# SCH_Sensor_circuit_design1_2023-04-27.net
KiCad netlist of a schematic drawn in EasyEDA
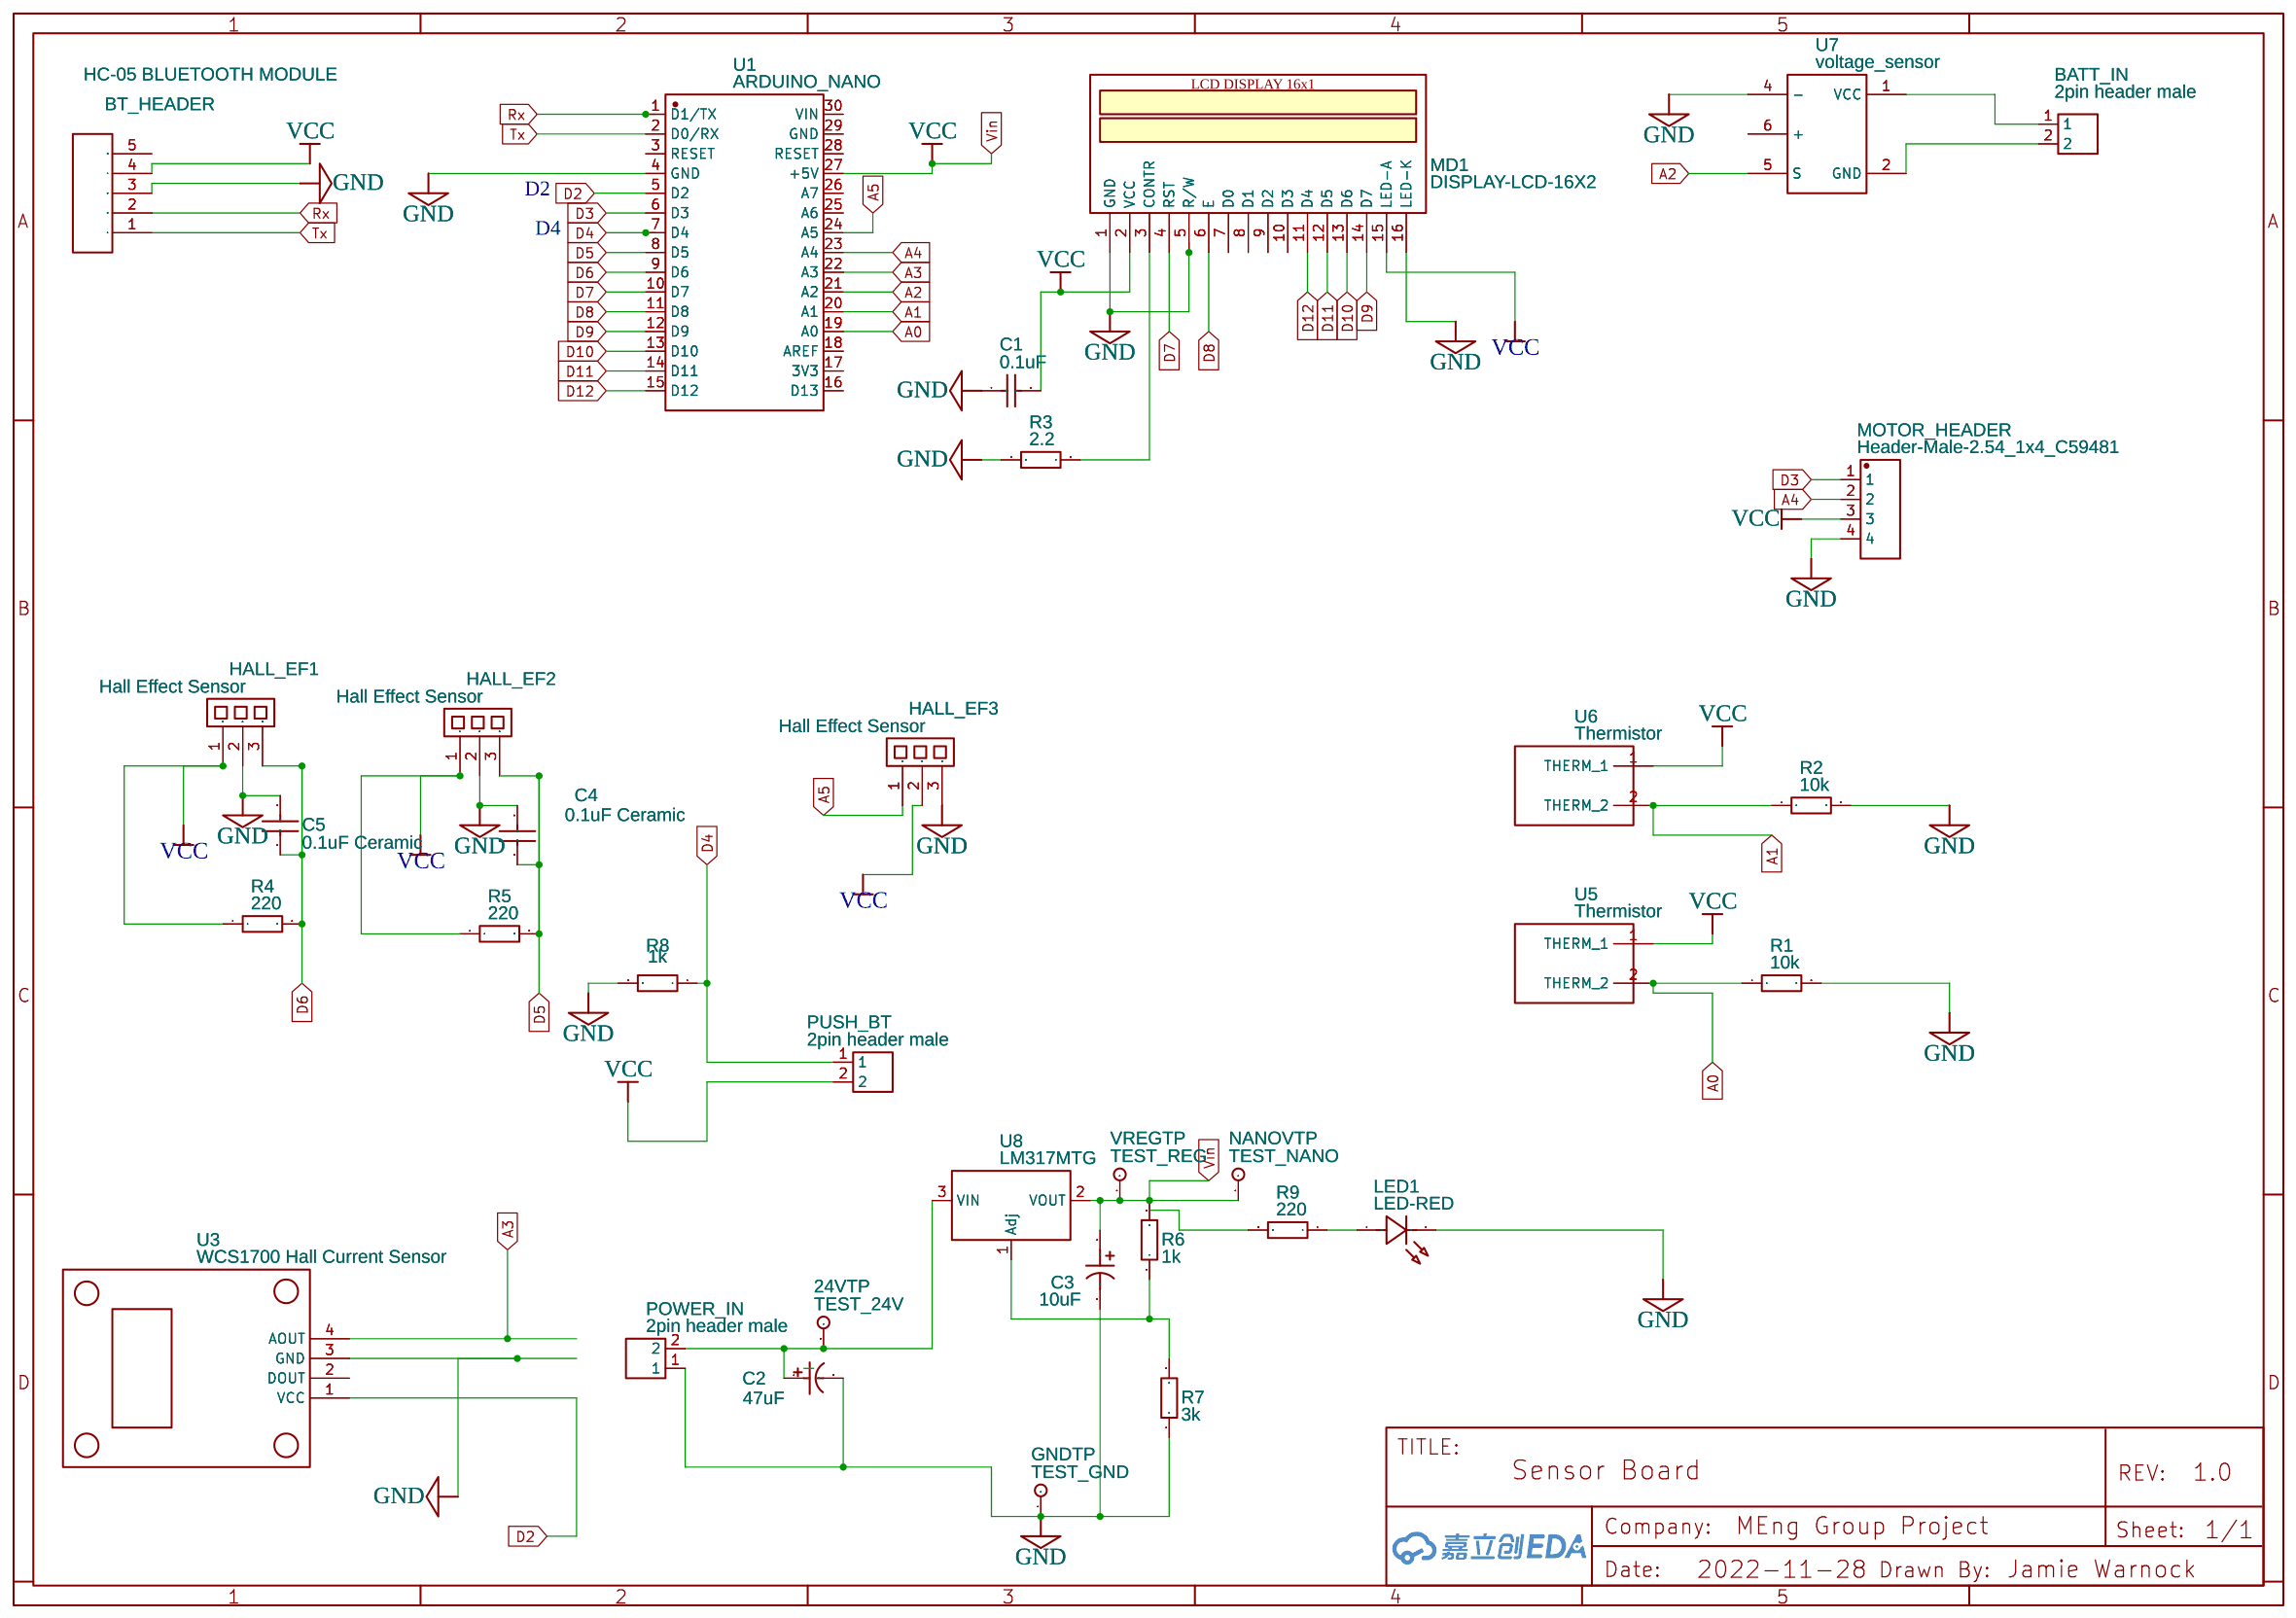
[diagram p0: schematic sheet]

(export (version "E")
  (design (tool "Eeschema 10.0.6"))
  (components
    (comp (ref "24VTP") (value "TEST_24V") (libsource (lib "") (part "TEST_1P_1")))
    (comp (ref "BATT_IN")
      (value "2pin header male")
      (fields
        (field (name "BOM_Manufacturer Part") "Headers  Pins2.54mm1*10P")
        (field (name "BOM_Supplier Part") "C57369")
      )
      (libsource (lib "") (part "2pin header male"))
    )
    (comp (ref "BT_HEADER")
      (value "HC-05 BLUETOOTH MODULE")
      (fields (field (name "BOM_Manufacturer Part") "New SchematicLib"))
      (libsource (lib "") (part "Female pin header 5 3D"))
    )
    (comp (ref "C1")
      (value "0.1uF")
      (fields (field (name "BOM_Manufacturer Part") "Ceramic capacitor0.1UF50V"))
      (libsource (lib "") (part "100NF CERAMIC CAPACITOR"))
    )
    (comp (ref "C2")
      (value "47uF")
      (fields (field (name "BOM_Manufacturer Part") "47uF 100V") (field (name "BOM_Supplier Part") "C36473"))
      (libsource (lib "") (part "v 47uF 100V"))
    )
    (comp (ref "C3")
      (value "10uF")
      (fields
        (field (name "BOM_Manufacturer Part") "50V10uF CD110")
        (field (name "BOM_Supplier Part") "C2960373")
      )
      (libsource (lib "") (part "50V10UF CD110_C2960373"))
    )
    (comp (ref "C4")
      (value "0.1uF Ceramic")
      (fields (field (name "BOM_Manufacturer Part") "Capacitor_Ceramic"))
      (libsource (lib "") (part "Capacitor_Ceramic"))
    )
    (comp (ref "C5")
      (value "0.1uF Ceramic")
      (fields (field (name "BOM_Manufacturer Part") "Capacitor_Ceramic"))
      (libsource (lib "") (part "Capacitor_Ceramic"))
    )
    (comp (ref "GNDTP") (value "TEST_GND") (libsource (lib "") (part "TEST_1P_3")))
    (comp (ref "HALL_EF1") (value "Hall Effect Sensor") (libsource (lib "") (part "HEADER MALE 1X3")))
    (comp (ref "HALL_EF2") (value "Hall Effect Sensor") (libsource (lib "") (part "HEADER MALE 1X3")))
    (comp (ref "HALL_EF3") (value "Hall Effect Sensor") (libsource (lib "") (part "HEADER MALE 1X3")))
    (comp (ref "LED1")
      (value "LED-RED")
      (fields (field (name "BOM_Manufacturer Part") "264-7ID") (field (name "BOM_Supplier Part") "C605466"))
      (libsource (lib "") (part "LED-RED"))
    )
    (comp (ref "MD1") (value "DISPLAY-LCD-16X2") (libsource (lib "") (part "DISPLAY-LCD-16X2")))
    (comp (ref "MOTOR_HEADER")
      (value "Header-Male-2.54_1x4_C59481")
      (fields
        (field (name "BOM_Manufacturer Part") "Headers  Pins 1*4P")
        (field (name "BOM_Supplier Part") "C59481")
      )
      (libsource (lib "") (part "Header-Male-2.54_1x4_C59481"))
    )
    (comp (ref "NANOVTP") (value "TEST_NANO") (libsource (lib "") (part "TEST_1P")))
    (comp (ref "POWER_IN")
      (value "2pin header male")
      (fields
        (field (name "BOM_Manufacturer Part") "Headers  Pins2.54mm1*10P")
        (field (name "BOM_Supplier Part") "C57369")
      )
      (libsource (lib "") (part "2pin header male_1"))
    )
    (comp (ref "PUSH_BT")
      (value "2pin header male")
      (fields
        (field (name "BOM_Manufacturer Part") "Headers  Pins2.54mm1*10P")
        (field (name "BOM_Supplier Part") "C57369")
      )
      (libsource (lib "") (part "2pin header male_2"))
    )
    (comp (ref "R1")
      (value "10k")
      (fields
        (field (name "BOM_Manufacturer Part") "EWWR0003J15R0T9")
        (field (name "BOM_Supplier Part") "C348853")
      )
      (libsource (lib "") (part "EWWR0003J15R0T9_1"))
    )
    (comp (ref "R2")
      (value "10k")
      (fields
        (field (name "BOM_Manufacturer Part") "EWWR0003J15R0T9")
        (field (name "BOM_Supplier Part") "C348853")
      )
      (libsource (lib "") (part "EWWR0003J15R0T9_1"))
    )
    (comp (ref "R3")
      (value "2.2")
      (fields
        (field (name "BOM_Manufacturer Part") "EWWR0003J2R20T9")
        (field (name "BOM_Supplier Part") "C348866")
      )
      (libsource (lib "") (part "EWWR0003J2R20T9"))
    )
    (comp (ref "R4")
      (value "220")
      (fields
        (field (name "BOM_Manufacturer Part") "EWWR0003J15R0T9")
        (field (name "BOM_Supplier Part") "C348853")
      )
      (libsource (lib "") (part "EWWR0003J15R0T9_1"))
    )
    (comp (ref "R5")
      (value "220")
      (fields
        (field (name "BOM_Manufacturer Part") "EWWR0003J15R0T9")
        (field (name "BOM_Supplier Part") "C348853")
      )
      (libsource (lib "") (part "EWWR0003J15R0T9_1"))
    )
    (comp (ref "R6")
      (value "1k")
      (fields
        (field (name "BOM_Manufacturer Part") "EWWR0003J15R0T9")
        (field (name "BOM_Supplier Part") "C348853")
      )
      (libsource (lib "") (part "EWWR0003J15R0T9_2"))
    )
    (comp (ref "R7")
      (value "3k")
      (fields
        (field (name "BOM_Manufacturer Part") "EWWR0003J15R0T9")
        (field (name "BOM_Supplier Part") "C348853")
      )
      (libsource (lib "") (part "EWWR0003J15R0T9_2"))
    )
    (comp (ref "R8")
      (value "1k")
      (fields
        (field (name "BOM_Manufacturer Part") "EWWR0003J15R0T9")
        (field (name "BOM_Supplier Part") "C348853")
      )
      (libsource (lib "") (part "EWWR0003J15R0T9"))
    )
    (comp (ref "R9")
      (value "220")
      (fields
        (field (name "BOM_Manufacturer Part") "EWWR0003J15R0T9")
        (field (name "BOM_Supplier Part") "C348853")
      )
      (libsource (lib "") (part "EWWR0003J15R0T9"))
    )
    (comp (ref "U1")
      (value "ARDUINO_NANO")
      (fields (field (name "BOM_Supplier Part") "C9900017879"))
      (libsource (lib "") (part "ARDUINO_NANO"))
    )
    (comp (ref "U3")
      (value "WCS1700 Hall Current Sensor")
      (fields (field (name "BOM_Supplier Part") "WCS1700"))
      (libsource (lib "") (part "WCS1700 Hall Current Sensor"))
    )
    (comp (ref "U5") (value "Thermistor") (libsource (lib "") (part "Thermistor")))
    (comp (ref "U6") (value "Thermistor") (libsource (lib "") (part "Thermistor")))
    (comp (ref "U7")
      (value "voltage_sensor")
      (fields
        (field (name "BOM_Manufacturer Part") "NMH1212SC")
        (field (name "BOM_Supplier Part") "811-1518-5-ND")
      )
      (libsource (lib "") (part "voltage_sensor"))
    )
    (comp (ref "U8")
      (value "LM317MTG")
      (fields (field (name "BOM_Supplier Part") "C907009"))
      (libsource (lib "") (part "LM317MTG"))
    )
    (comp (ref "VREGTP") (value "TEST_REG") (libsource (lib "") (part "TEST_1P_2")))
  )
  (nets
    (net (code "1") (name "A0") (class "Default")
      (node (ref "R1") (pin "1") (pinfunction "1_1") (pintype "unspecified"))
      (node (ref "U1") (pin "19") (pinfunction "A0_19") (pintype "unspecified"))
      (node (ref "U5") (pin "2") (pinfunction "THERM_2_2") (pintype "unspecified"))
    )
    (net (code "2") (name "A1") (class "Default")
      (node (ref "R2") (pin "1") (pinfunction "1_1") (pintype "unspecified"))
      (node (ref "U1") (pin "20") (pinfunction "A1_20") (pintype "unspecified"))
      (node (ref "U6") (pin "2") (pinfunction "THERM_2_2") (pintype "unspecified"))
    )
    (net (code "3") (name "A2") (class "Default")
      (node (ref "U1") (pin "21") (pinfunction "A2_21") (pintype "unspecified"))
      (node (ref "U7") (pin "5") (pinfunction "S_5") (pintype "unspecified"))
    )
    (net (code "4") (name "A3") (class "Default")
      (node (ref "U1") (pin "22") (pinfunction "A3_22") (pintype "unspecified"))
      (node (ref "U3") (pin "4") (pinfunction "AOUT_4") (pintype "unspecified"))
    )
    (net (code "5") (name "A4") (class "Default")
      (node (ref "MOTOR_HEADER") (pin "2") (pinfunction "2_2") (pintype "unspecified"))
      (node (ref "U1") (pin "23") (pinfunction "A4_23") (pintype "unspecified"))
    )
    (net (code "6") (name "A5") (class "Default")
      (node (ref "HALL_EF3") (pin "1") (pinfunction "1_1") (pintype "unspecified"))
      (node (ref "U1") (pin "24") (pinfunction "A5_24") (pintype "unspecified"))
    )
    (net (code "7") (name "D2") (class "Default")
      (node (ref "U1") (pin "5") (pinfunction "D2_5") (pintype "unspecified"))
      (node (ref "U3") (pin "1") (pinfunction "VCC_1") (pintype "unspecified"))
    )
    (net (code "8") (name "D3") (class "Default")
      (node (ref "MOTOR_HEADER") (pin "1") (pinfunction "1_1") (pintype "unspecified"))
      (node (ref "U1") (pin "6") (pinfunction "D3_6") (pintype "unspecified"))
    )
    (net (code "9") (name "D4") (class "Default")
      (node (ref "PUSH_BT") (pin "1") (pinfunction "1_1") (pintype "unspecified"))
      (node (ref "R8") (pin "1") (pinfunction "1_1") (pintype "unspecified"))
      (node (ref "U1") (pin "7") (pinfunction "D4_7") (pintype "unspecified"))
    )
    (net (code "10") (name "D5") (class "Default")
      (node (ref "C4") (pin "1") (pinfunction "1_1") (pintype "unspecified"))
      (node (ref "HALL_EF2") (pin "3") (pinfunction "3_3") (pintype "unspecified"))
      (node (ref "R5") (pin "2") (pinfunction "2_2") (pintype "unspecified"))
      (node (ref "U1") (pin "8") (pinfunction "D5_8") (pintype "unspecified"))
    )
    (net (code "11") (name "D6") (class "Default")
      (node (ref "C5") (pin "1") (pinfunction "1_1") (pintype "unspecified"))
      (node (ref "HALL_EF1") (pin "3") (pinfunction "3_3") (pintype "unspecified"))
      (node (ref "R4") (pin "2") (pinfunction "2_2") (pintype "unspecified"))
      (node (ref "U1") (pin "9") (pinfunction "D6_9") (pintype "unspecified"))
    )
    (net (code "12") (name "D7") (class "Default")
      (node (ref "MD1") (pin "4") (pinfunction "RST_4") (pintype "unspecified"))
      (node (ref "U1") (pin "10") (pinfunction "D7_10") (pintype "unspecified"))
    )
    (net (code "13") (name "D8") (class "Default")
      (node (ref "MD1") (pin "6") (pinfunction "E_6") (pintype "unspecified"))
      (node (ref "U1") (pin "11") (pinfunction "D8_11") (pintype "unspecified"))
    )
    (net (code "14") (name "D9") (class "Default")
      (node (ref "MD1") (pin "14") (pinfunction "D7_14") (pintype "unspecified"))
      (node (ref "U1") (pin "12") (pinfunction "D9_12") (pintype "unspecified"))
    )
    (net (code "15") (name "D10") (class "Default")
      (node (ref "MD1") (pin "13") (pinfunction "D6_13") (pintype "unspecified"))
      (node (ref "U1") (pin "13") (pinfunction "D10_13") (pintype "unspecified"))
    )
    (net (code "16") (name "D11") (class "Default")
      (node (ref "MD1") (pin "12") (pinfunction "D5_12") (pintype "unspecified"))
      (node (ref "U1") (pin "14") (pinfunction "D11_14") (pintype "unspecified"))
    )
    (net (code "17") (name "D12") (class "Default")
      (node (ref "MD1") (pin "11") (pinfunction "D4_11") (pintype "unspecified"))
      (node (ref "U1") (pin "15") (pinfunction "D12_15") (pintype "unspecified"))
    )
    (net (code "18") (name "GND") (class "Default")
      (node (ref "BT_HEADER") (pin "3") (pinfunction "3_3") (pintype "unspecified"))
      (node (ref "C1") (pin "1") (pinfunction "1_1") (pintype "input"))
      (node (ref "C2") (pin "2") (pinfunction "2_2") (pintype "input"))
      (node (ref "C3") (pin "2") (pinfunction "2_2") (pintype "input"))
      (node (ref "C4") (pin "2") (pinfunction "2_2") (pintype "unspecified"))
      (node (ref "C5") (pin "2") (pinfunction "2_2") (pintype "unspecified"))
      (node (ref "GNDTP") (pin "1") (pinfunction "1_1") (pintype "unspecified"))
      (node (ref "HALL_EF1") (pin "2") (pinfunction "2_2") (pintype "unspecified"))
      (node (ref "HALL_EF2") (pin "2") (pinfunction "2_2") (pintype "unspecified"))
      (node (ref "HALL_EF3") (pin "3") (pinfunction "3_3") (pintype "unspecified"))
      (node (ref "LED1") (pin "2") (pinfunction "K_2") (pintype "unspecified"))
      (node (ref "MD1") (pin "1") (pinfunction "GND_1") (pintype "unspecified"))
      (node (ref "MD1") (pin "16") (pinfunction "LED-K_16") (pintype "unspecified"))
      (node (ref "MD1") (pin "5") (pinfunction "R/W_5") (pintype "unspecified"))
      (node (ref "MOTOR_HEADER") (pin "4") (pinfunction "4_4") (pintype "unspecified"))
      (node (ref "POWER_IN") (pin "1") (pinfunction "1_1") (pintype "unspecified"))
      (node (ref "R1") (pin "2") (pinfunction "2_2") (pintype "unspecified"))
      (node (ref "R2") (pin "2") (pinfunction "2_2") (pintype "unspecified"))
      (node (ref "R3") (pin "1") (pinfunction "1_1") (pintype "unspecified"))
      (node (ref "R7") (pin "1") (pinfunction "1_1") (pintype "unspecified"))
      (node (ref "R8") (pin "2") (pinfunction "2_2") (pintype "unspecified"))
      (node (ref "U1") (pin "4") (pinfunction "GND_4") (pintype "unspecified"))
      (node (ref "U3") (pin "3") (pinfunction "GND_3") (pintype "unspecified"))
      (node (ref "U7") (pin "4") (pinfunction "-_4") (pintype "unspecified"))
    )
    (net (code "19") (name "Net-(LED1-A)") (class "Default")
      (node (ref "LED1") (pin "1") (pinfunction "A_1") (pintype "unspecified"))
      (node (ref "R9") (pin "1") (pinfunction "1_1") (pintype "unspecified"))
    )
    (net (code "20") (name "Net-(MD1-CONTR)") (class "Default")
      (node (ref "MD1") (pin "3") (pinfunction "CONTR_3") (pintype "unspecified"))
      (node (ref "R3") (pin "2") (pinfunction "2_2") (pintype "unspecified"))
    )
    (net (code "21") (name "Net-(U7-GND)") (class "Default")
      (node (ref "BATT_IN") (pin "2") (pinfunction "2_2") (pintype "unspecified"))
      (node (ref "U7") (pin "2") (pinfunction "GND_2") (pintype "unspecified"))
    )
    (net (code "22") (name "Net-(U7-VCC)") (class "Default")
      (node (ref "BATT_IN") (pin "1") (pinfunction "1_1") (pintype "unspecified"))
      (node (ref "U7") (pin "1") (pinfunction "VCC_1") (pintype "unspecified"))
    )
    (net (code "23") (name "Net-(U8-Adj)") (class "Default")
      (node (ref "R6") (pin "1") (pinfunction "1_1") (pintype "unspecified"))
      (node (ref "R7") (pin "2") (pinfunction "2_2") (pintype "unspecified"))
      (node (ref "U8") (pin "1") (pinfunction "Adj_1") (pintype "unspecified"))
    )
    (net (code "24") (name "Net-(U8-VIN)") (class "Default")
      (node (ref "24VTP") (pin "1") (pinfunction "1_1") (pintype "unspecified"))
      (node (ref "C2") (pin "1") (pinfunction "1_1") (pintype "input"))
      (node (ref "POWER_IN") (pin "2") (pinfunction "2_2") (pintype "unspecified"))
      (node (ref "U8") (pin "3") (pinfunction "VIN_3") (pintype "unspecified"))
    )
    (net (code "25") (name "Rx") (class "Default")
      (node (ref "BT_HEADER") (pin "2") (pinfunction "2_2") (pintype "unspecified"))
      (node (ref "U1") (pin "1") (pinfunction "D1/TX_1") (pintype "unspecified"))
    )
    (net (code "26") (name "Tx") (class "Default")
      (node (ref "BT_HEADER") (pin "1") (pinfunction "1_1") (pintype "unspecified"))
      (node (ref "U1") (pin "2") (pinfunction "D0/RX_2") (pintype "unspecified"))
    )
    (net (code "27") (name "Vin") (class "Default")
      (node (ref "BT_HEADER") (pin "4") (pinfunction "4_4") (pintype "unspecified"))
      (node (ref "C1") (pin "2") (pinfunction "2_2") (pintype "input"))
      (node (ref "C3") (pin "1") (pinfunction "1_1") (pintype "input"))
      (node (ref "HALL_EF1") (pin "1") (pinfunction "1_1") (pintype "unspecified"))
      (node (ref "HALL_EF2") (pin "1") (pinfunction "1_1") (pintype "unspecified"))
      (node (ref "HALL_EF3") (pin "2") (pinfunction "2_2") (pintype "unspecified"))
      (node (ref "MD1") (pin "15") (pinfunction "LED-A_15") (pintype "unspecified"))
      (node (ref "MD1") (pin "2") (pinfunction "VCC_2") (pintype "unspecified"))
      (node (ref "MOTOR_HEADER") (pin "3") (pinfunction "3_3") (pintype "unspecified"))
      (node (ref "NANOVTP") (pin "1") (pinfunction "1_1") (pintype "unspecified"))
      (node (ref "PUSH_BT") (pin "2") (pinfunction "2_2") (pintype "unspecified"))
      (node (ref "R4") (pin "1") (pinfunction "1_1") (pintype "unspecified"))
      (node (ref "R5") (pin "1") (pinfunction "1_1") (pintype "unspecified"))
      (node (ref "R6") (pin "2") (pinfunction "2_2") (pintype "unspecified"))
      (node (ref "R9") (pin "2") (pinfunction "2_2") (pintype "unspecified"))
      (node (ref "U1") (pin "27") (pinfunction "+5V_27") (pintype "unspecified"))
      (node (ref "U5") (pin "1") (pinfunction "THERM_1_1") (pintype "unspecified"))
      (node (ref "U6") (pin "1") (pinfunction "THERM_1_1") (pintype "unspecified"))
      (node (ref "U8") (pin "2") (pinfunction "VOUT_2") (pintype "unspecified"))
      (node (ref "VREGTP") (pin "1") (pinfunction "1_1") (pintype "unspecified"))
    )
    (net (code "28") (name "unconnected-(BT_HEADER-Pad5)") (class "Default")
      (node (ref "BT_HEADER") (pin "5") (pinfunction "5_5") (pintype "unspecified"))
    )
    (net (code "29") (name "unconnected-(MD1-D0-Pad7)") (class "Default")
      (node (ref "MD1") (pin "7") (pinfunction "D0_7") (pintype "unspecified"))
    )
    (net (code "30") (name "unconnected-(MD1-D1-Pad8)") (class "Default")
      (node (ref "MD1") (pin "8") (pinfunction "D1_8") (pintype "unspecified"))
    )
    (net (code "31") (name "unconnected-(MD1-D2-Pad9)") (class "Default")
      (node (ref "MD1") (pin "9") (pinfunction "D2_9") (pintype "unspecified"))
    )
    (net (code "32") (name "unconnected-(MD1-D3-Pad10)") (class "Default")
      (node (ref "MD1") (pin "10") (pinfunction "D3_10") (pintype "unspecified"))
    )
    (net (code "33") (name "unconnected-(U1-3V3-Pad17)") (class "Default")
      (node (ref "U1") (pin "17") (pinfunction "3V3_17") (pintype "unspecified"))
    )
    (net (code "34") (name "unconnected-(U1-A6-Pad25)") (class "Default")
      (node (ref "U1") (pin "25") (pinfunction "A6_25") (pintype "unspecified"))
    )
    (net (code "35") (name "unconnected-(U1-A7-Pad26)") (class "Default")
      (node (ref "U1") (pin "26") (pinfunction "A7_26") (pintype "unspecified"))
    )
    (net (code "36") (name "unconnected-(U1-AREF-Pad18)") (class "Default")
      (node (ref "U1") (pin "18") (pinfunction "AREF_18") (pintype "unspecified"))
    )
    (net (code "37") (name "unconnected-(U1-D13-Pad16)") (class "Default")
      (node (ref "U1") (pin "16") (pinfunction "D13_16") (pintype "unspecified"))
    )
    (net (code "38") (name "unconnected-(U1-GND-Pad29)") (class "Default")
      (node (ref "U1") (pin "29") (pinfunction "GND_29") (pintype "unspecified"))
    )
    (net (code "39") (name "unconnected-(U1-RESET-Pad3)") (class "Default")
      (node (ref "U1") (pin "3") (pinfunction "RESET_3") (pintype "unspecified"))
    )
    (net (code "40") (name "unconnected-(U1-RESET-Pad28)") (class "Default")
      (node (ref "U1") (pin "28") (pinfunction "RESET_28") (pintype "unspecified"))
    )
    (net (code "41") (name "unconnected-(U1-VIN-Pad30)") (class "Default")
      (node (ref "U1") (pin "30") (pinfunction "VIN_30") (pintype "unspecified"))
    )
    (net (code "42") (name "unconnected-(U3-DOUT-Pad2)") (class "Default")
      (node (ref "U3") (pin "2") (pinfunction "DOUT_2") (pintype "unspecified"))
    )
    (net (code "43") (name "unconnected-(U7-+-Pad6)") (class "Default")
      (node (ref "U7") (pin "6") (pinfunction "+_6") (pintype "unspecified"))
    )
  )
)
